# Sensor.net
KiCad netlist of a schematic drawn in EAGLE
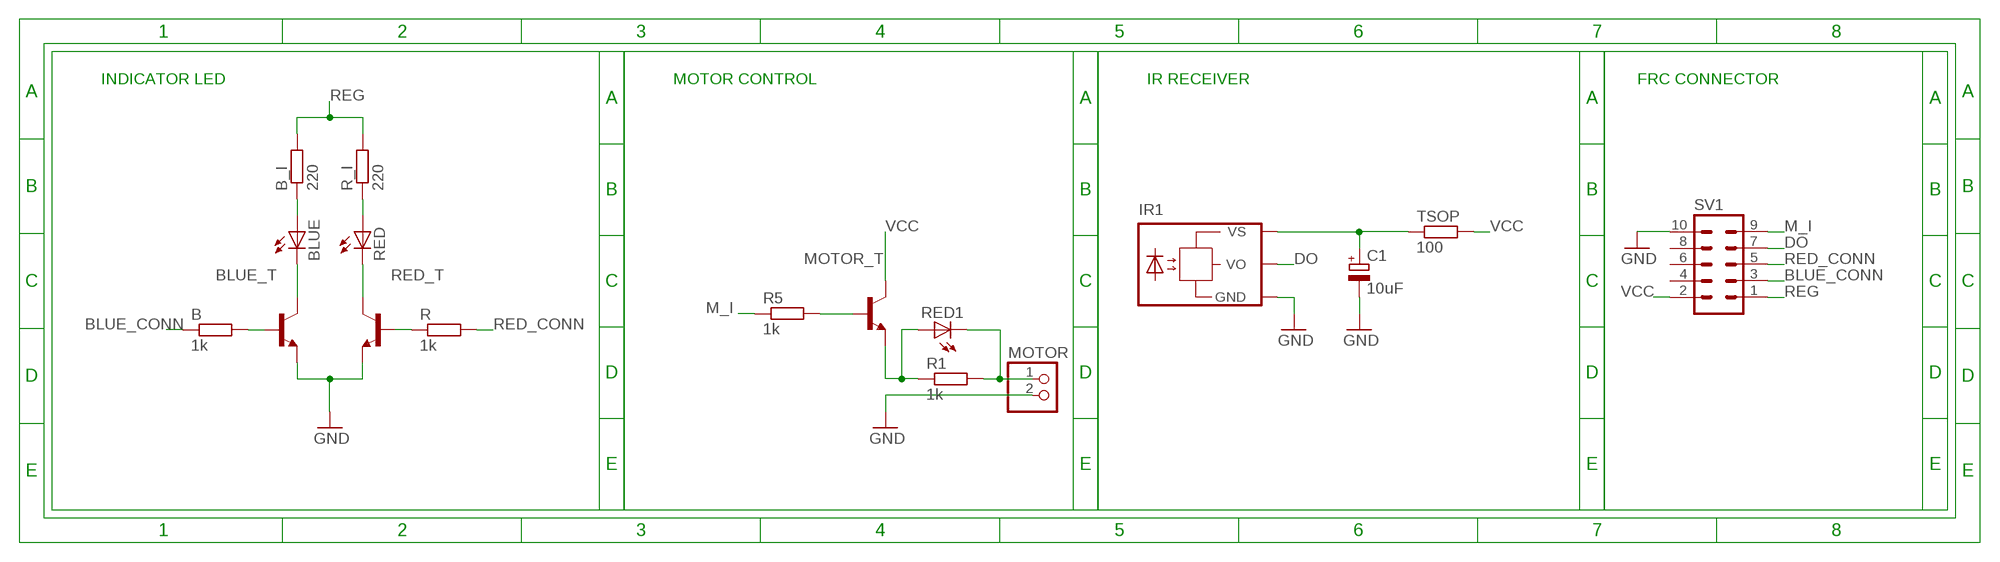
[diagram p0: schematic, sheet 1]

(export (version "E")
  (design (tool "Eeschema 10.0.6"))
  (components
    (comp (ref "B")
      (value "1k")
      (footprint "eagle-import:0207_12")
      (libsource (lib "eagle-import") (part "R-EU_0207/12"))
    )
    (comp (ref "BLUE")
      (value "LED5MM")
      (footprint "eagle-import:LED5MM")
      (libsource (lib "eagle-import") (part "LED5MM"))
    )
    (comp (ref "BLUE_T")
      (value "BC547")
      (footprint "eagle-import:TO92")
      (libsource (lib "eagle-import") (part "BC547"))
    )
    (comp (ref "B_I")
      (value "220")
      (footprint "eagle-import:0207_12")
      (libsource (lib "eagle-import") (part "R-EU_0207/12"))
    )
    (comp (ref "C1")
      (value "10uF")
      (footprint "eagle-import:E2,5-6")
      (libsource (lib "eagle-import") (part "CPOL-EUE2.5-6"))
    )
    (comp (ref "IR1")
      (value "TSOP1730TB1")
      (footprint "eagle-import:TSOP17_TB1")
      (libsource (lib "eagle-import") (part "TSOP17TB130"))
    )
    (comp (ref "MOTOR")
      (value "PINHD-1X2")
      (footprint "eagle-import:1X02")
      (libsource (lib "eagle-import") (part "PINHD-1X2"))
    )
    (comp (ref "MOTOR_T")
      (value "BC547")
      (footprint "eagle-import:TO92")
      (libsource (lib "eagle-import") (part "BC547"))
    )
    (comp (ref "R")
      (value "1k")
      (footprint "eagle-import:0207_12")
      (libsource (lib "eagle-import") (part "R-EU_0207/12"))
    )
    (comp (ref "R1")
      (value "1k")
      (footprint "eagle-import:0207_12")
      (libsource (lib "eagle-import") (part "R-EU_0207/12"))
    )
    (comp (ref "R5")
      (value "1k")
      (footprint "eagle-import:0207_12")
      (libsource (lib "eagle-import") (part "R-EU_0207/12"))
    )
    (comp (ref "RED")
      (value "LED5MM")
      (footprint "eagle-import:LED5MM")
      (libsource (lib "eagle-import") (part "LED5MM"))
    )
    (comp (ref "RED1")
      (value "LEDSMT1206")
      (footprint "eagle-import:1206")
      (libsource (lib "eagle-import") (part "LEDSMT1206"))
    )
    (comp (ref "RED_T")
      (value "BC547")
      (footprint "eagle-import:TO92")
      (libsource (lib "eagle-import") (part "BC547"))
    )
    (comp (ref "R_I")
      (value "220")
      (footprint "eagle-import:0207_12")
      (libsource (lib "eagle-import") (part "R-EU_0207/12"))
    )
    (comp (ref "SV1")
      (value "ML10")
      (footprint "eagle-import:ML10")
      (libsource (lib "eagle-import") (part "ML10"))
    )
    (comp (ref "TSOP")
      (value "100")
      (footprint "eagle-import:0207_12")
      (libsource (lib "eagle-import") (part "R-EU_0207/12"))
    )
  )
  (nets
    (net (code "1") (name "/BLUE_CONN") (class "Default")
      (node (ref "B") (pin "1") (pinfunction "1_1") (pintype "passive"))
      (node (ref "SV1") (pin "3") (pinfunction "3_3") (pintype "passive"))
    )
    (net (code "2") (name "/DO") (class "Default")
      (node (ref "IR1") (pin "VO") (pinfunction "VO_VO") (pintype "open_collector"))
      (node (ref "SV1") (pin "7") (pinfunction "7_7") (pintype "passive"))
    )
    (net (code "3") (name "/M_I") (class "Default")
      (node (ref "R5") (pin "1") (pinfunction "1_1") (pintype "passive"))
      (node (ref "SV1") (pin "9") (pinfunction "9_9") (pintype "passive"))
    )
    (net (code "4") (name "/RED_CONN") (class "Default")
      (node (ref "R") (pin "2") (pinfunction "2_2") (pintype "passive"))
      (node (ref "SV1") (pin "5") (pinfunction "5_5") (pintype "passive"))
    )
    (net (code "5") (name "/REG") (class "Default")
      (node (ref "B_I") (pin "2") (pinfunction "2_2") (pintype "passive"))
      (node (ref "R_I") (pin "2") (pinfunction "2_2") (pintype "passive"))
      (node (ref "SV1") (pin "1") (pinfunction "1_1") (pintype "passive"))
    )
    (net (code "6") (name "/VCC") (class "Default")
      (node (ref "MOTOR_T") (pin "3") (pinfunction "C_3") (pintype "passive"))
      (node (ref "SV1") (pin "2") (pinfunction "2_2") (pintype "passive"))
      (node (ref "TSOP") (pin "2") (pinfunction "2_2") (pintype "passive"))
    )
    (net (code "7") (name "GND") (class "Default")
      (node (ref "BLUE_T") (pin "1") (pinfunction "E_1") (pintype "passive"))
      (node (ref "C1") (pin "-") (pinfunction "-_-") (pintype "passive"))
      (node (ref "IR1") (pin "GND") (pinfunction "GND_GND") (pintype "power_in"))
      (node (ref "MOTOR") (pin "2") (pinfunction "2_2") (pintype "passive"))
      (node (ref "RED_T") (pin "1") (pinfunction "E_1") (pintype "passive"))
      (node (ref "SV1") (pin "10") (pinfunction "10_10") (pintype "passive"))
    )
    (net (code "8") (name "Net-(BLUE-C)") (class "Default")
      (node (ref "BLUE") (pin "K") (pinfunction "C_K") (pintype "passive"))
      (node (ref "BLUE_T") (pin "3") (pinfunction "C_3") (pintype "passive"))
    )
    (net (code "9") (name "Net-(BLUE-PadA)") (class "Default")
      (node (ref "BLUE") (pin "A") (pinfunction "A_A") (pintype "passive"))
      (node (ref "B_I") (pin "1") (pinfunction "1_1") (pintype "passive"))
    )
    (net (code "10") (name "Net-(BLUE_T-B)") (class "Default")
      (node (ref "B") (pin "2") (pinfunction "2_2") (pintype "passive"))
      (node (ref "BLUE_T") (pin "2") (pinfunction "B_2") (pintype "passive"))
    )
    (net (code "11") (name "Net-(C1-Pad+)") (class "Default")
      (node (ref "C1") (pin "+") (pinfunction "+_+") (pintype "passive"))
      (node (ref "IR1") (pin "VS") (pinfunction "VS_VS") (pintype "power_in"))
      (node (ref "TSOP") (pin "1") (pinfunction "1_1") (pintype "passive"))
    )
    (net (code "12") (name "Net-(MOTOR-Pad1)") (class "Default")
      (node (ref "MOTOR") (pin "1") (pinfunction "1_1") (pintype "passive"))
      (node (ref "R1") (pin "2") (pinfunction "2_2") (pintype "passive"))
      (node (ref "RED1") (pin "C") (pinfunction "C_C") (pintype "passive"))
    )
    (net (code "13") (name "Net-(MOTOR_T-B)") (class "Default")
      (node (ref "MOTOR_T") (pin "2") (pinfunction "B_2") (pintype "passive"))
      (node (ref "R5") (pin "2") (pinfunction "2_2") (pintype "passive"))
    )
    (net (code "14") (name "Net-(MOTOR_T-E)") (class "Default")
      (node (ref "MOTOR_T") (pin "1") (pinfunction "E_1") (pintype "passive"))
      (node (ref "R1") (pin "1") (pinfunction "1_1") (pintype "passive"))
      (node (ref "RED1") (pin "A") (pinfunction "A_A") (pintype "passive"))
    )
    (net (code "15") (name "Net-(RED-C)") (class "Default")
      (node (ref "RED") (pin "K") (pinfunction "C_K") (pintype "passive"))
      (node (ref "RED_T") (pin "3") (pinfunction "C_3") (pintype "passive"))
    )
    (net (code "16") (name "Net-(RED-PadA)") (class "Default")
      (node (ref "RED") (pin "A") (pinfunction "A_A") (pintype "passive"))
      (node (ref "R_I") (pin "1") (pinfunction "1_1") (pintype "passive"))
    )
    (net (code "17") (name "Net-(RED_T-B)") (class "Default")
      (node (ref "R") (pin "1") (pinfunction "1_1") (pintype "passive"))
      (node (ref "RED_T") (pin "2") (pinfunction "B_2") (pintype "passive"))
    )
    (net (code "18") (name "unconnected-(SV1-Pad4)") (class "Default")
      (node (ref "SV1") (pin "4") (pinfunction "4_4") (pintype "passive"))
    )
    (net (code "19") (name "unconnected-(SV1-Pad6)") (class "Default")
      (node (ref "SV1") (pin "6") (pinfunction "6_6") (pintype "passive"))
    )
    (net (code "20") (name "unconnected-(SV1-Pad8)") (class "Default")
      (node (ref "SV1") (pin "8") (pinfunction "8_8") (pintype "passive"))
    )
  )
)
